# Master_Micro.net
KiCad netlist of a schematic drawn in Altium Designer
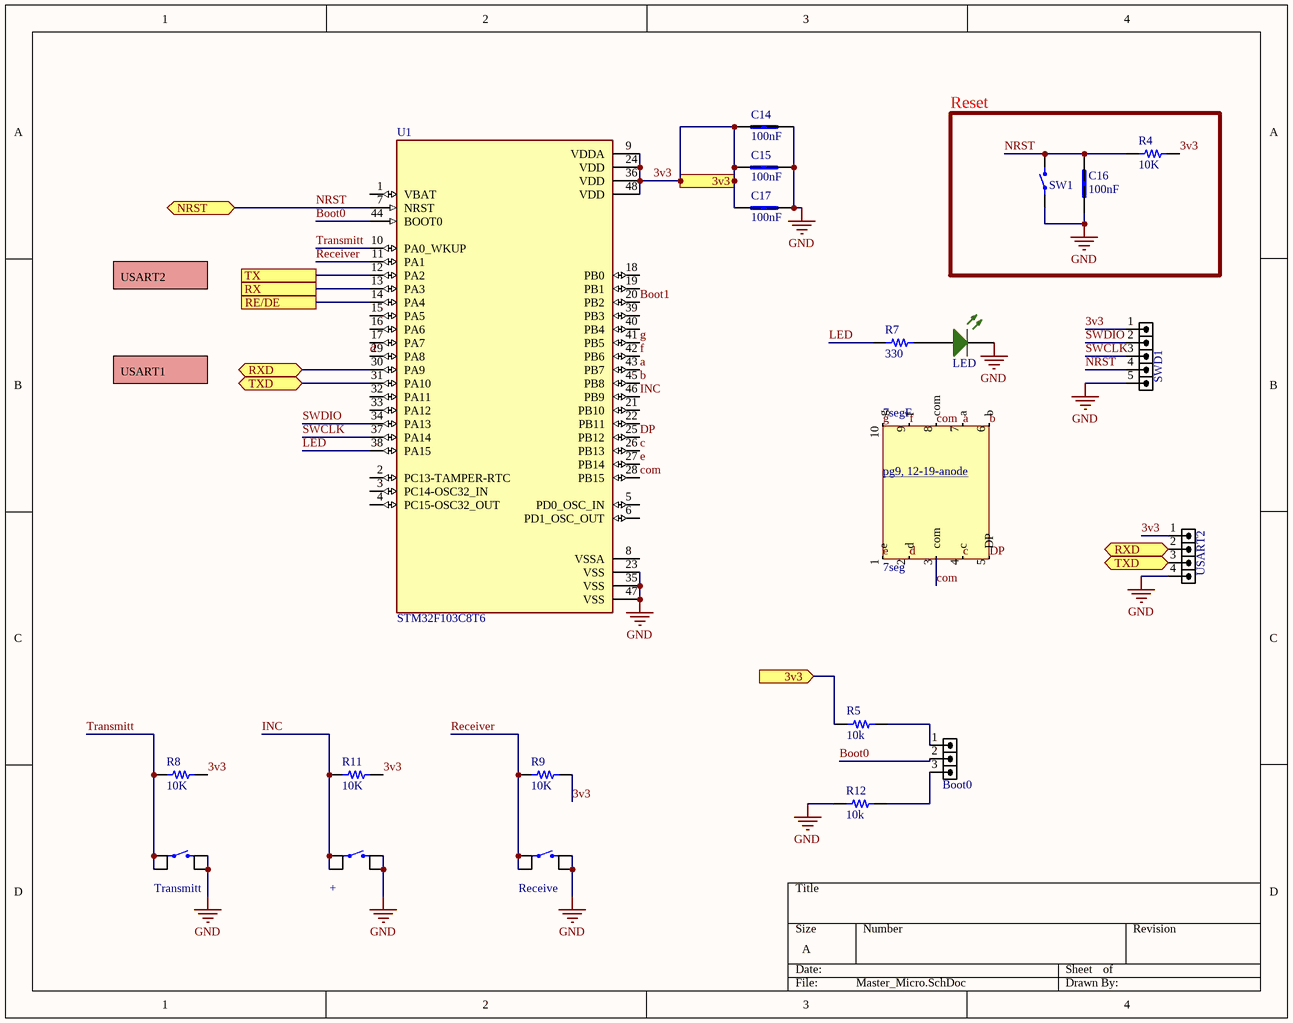
[diagram p0: Master_Micro.SchDoc]

(export (version "E")
  (design (tool "Eeschema 10.0.6"))
  (components
    (comp (ref "+")
      (value "Tactile 4PIN 6X6mm H5mm (THD)")
      (footprint "SWPBT_SPDT_6X6X5SKHH")
      (description "Tactile Switch SPST-NO Top Actuated Surface Mount")
      (fields (field (name "PARTNUMBER") "PTS645SH50SMTR92 LFS"))
      (libsource (lib "Switch") (part "Tactile 4PIN 6X6mm H5mm (THD)"))
    )
    (comp (ref "7seg")
      (value "7seg")
      (footprint "PCBComponent_1 - duplicate")
      (description "file:///C:/Users/Tamana/Downloads/7SEG-12-19mm-GREEN-ANOD.pdf")
      (libsource (lib "7seg") (part "7seg"))
    )
    (comp (ref "Boot0")
      (value "HDRM3")
      (footprint "HDR_1X3")
      (description "CONN, HEADER, Male, pitch: 2.54mm, 3POS")
      (libsource (lib "Conn Header") (part "HDR_1X3"))
    )
    (comp (ref "C14")
      (value "100nF")
      (footprint "CAP 0805_2012")
      (description "COMMERCIAL CHIP STD JAPAN BULK - FN TAPE/REEL, 7 INCH PAPER TAPE-0805")
      (fields (field (name "MP") "LD051C182KAB2A"))
      (libsource (lib "cap 0805") (part "LD051C182KAB2A"))
    )
    (comp (ref "C15")
      (value "100nF")
      (footprint "CAP 0805_2012")
      (description "COMMERCIAL CHIP STD JAPAN BULK - FN TAPE/REEL, 7 INCH PAPER TAPE-0805")
      (fields (field (name "MP") "LD051C182KAB2A"))
      (libsource (lib "cap 0805") (part "LD051C182KAB2A"))
    )
    (comp (ref "C16")
      (value "100nF")
      (footprint "CAP 0805_2012")
      (description "COMMERCIAL CHIP STD JAPAN BULK - FN TAPE/REEL, 7 INCH PAPER TAPE-0805")
      (fields (field (name "MP") "LD051C182KAB2A"))
      (libsource (lib "") (part "LD051C182KAB2A_1"))
    )
    (comp (ref "C17")
      (value "100nF")
      (footprint "CAP 0805_2012")
      (description "COMMERCIAL CHIP STD JAPAN BULK - FN TAPE/REEL, 7 INCH PAPER TAPE-0805")
      (fields (field (name "MP") "LD051C182KAB2A"))
      (libsource (lib "cap 0805") (part "LD051C182KAB2A"))
    )
    (comp (ref "LED")
      (value "LED SMD 0805 GREEN")
      (footprint "LED_0805_GREEN")
      (libsource (lib "Led") (part "LED SMD 0805 GREEN"))
    )
    (comp (ref "R4")
      (value "10K")
      (footprint "RES 0805_2012")
      (description "SMT Resistor")
      (libsource (lib "Resistor") (part "Res 0805"))
    )
    (comp (ref "R5")
      (value "10k")
      (footprint "RES 0805_2012")
      (description "SMT Resistor")
      (libsource (lib "Resistor") (part "Res 0805"))
    )
    (comp (ref "R7")
      (value "330")
      (footprint "RES 0805_2012")
      (description "SMT Resistor")
      (libsource (lib "Resistor") (part "Res 0805"))
    )
    (comp (ref "R8")
      (value "10K")
      (footprint "RES 0805_2012")
      (description "SMT Resistor")
      (libsource (lib "Resistor") (part "Res 0805"))
    )
    (comp (ref "R9")
      (value "10K")
      (footprint "RES 0805_2012")
      (description "SMT Resistor")
      (libsource (lib "Resistor") (part "Res 0805"))
    )
    (comp (ref "R11")
      (value "10K")
      (footprint "RES 0805_2012")
      (description "SMT Resistor")
      (libsource (lib "Resistor") (part "Res 0805"))
    )
    (comp (ref "R12")
      (value "10k")
      (footprint "RES 0805_2012")
      (description "SMT Resistor")
      (libsource (lib "Resistor") (part "Res 0805"))
    )
    (comp (ref "Receive")
      (value "Tactile 4PIN 6X6mm H5mm (THD)")
      (footprint "SWPBT_SPDT_6X6X5SKHH")
      (description "Tactile Switch SPST-NO Top Actuated Surface Mount")
      (fields (field (name "PARTNUMBER") "PTS645SH50SMTR92 LFS"))
      (libsource (lib "Switch") (part "Tactile 4PIN 6X6mm H5mm (THD)"))
    )
    (comp (ref "SW1")
      (value "Tactile 2PIN 6X3.5mm H4.57mm (SMD)")
      (footprint "SWPBS_SPST_6X3X5")
      (description "Tactile Switch SPST-NO Top Actuated Surface Mount")
      (fields (field (name "PARTNUMBER") "FSMSMTR-ND"))
      (libsource (lib "Switch") (part "Tactile 2PIN 6X3.5mm H4.57mm (SMD)"))
    )
    (comp (ref "SWD1")
      (value "HDR1X5")
      (footprint "HDR_1X5")
      (description "CONN, HEADER, Male, pitch: 2.54mm, 5POS")
      (libsource (lib "Conn Header") (part "HDR_1X5"))
    )
    (comp (ref "Transmitt")
      (value "Tactile 4PIN 6X6mm H5mm (THD)")
      (footprint "SWPBT_SPDT_6X6X5SKHH")
      (description "Tactile Switch SPST-NO Top Actuated Surface Mount")
      (fields (field (name "PARTNUMBER") "PTS645SH50SMTR92 LFS"))
      (libsource (lib "Switch") (part "Tactile 4PIN 6X6mm H5mm (THD)"))
    )
    (comp (ref "U1")
      (value "STM32F103C8T6")
      (footprint "QFP50P900X900X160-48N")
      (description "ARM® Cortex®-M3 STM32F1 Microcontroller IC 32-Bit 72MHz 64KB (64K x 8) FLASH 48-LQFP (7x7)")
      (fields (field (name "MF") "STMicroelectronics"))
      (libsource (lib "STM32F103C8T6") (part "STM32F103C8T6"))
    )
    (comp (ref "USART2")
      (value "HDR1X4")
      (footprint "HDR_1X4")
      (description "CONN, HEADER, Male, pitch: 2.54mm, 4POS")
      (libsource (lib "Conn Header") (part "HDR_1X4"))
    )
  )
  (nets
    (net (code "1") (name "/3v3") (class "Default")
      (node (ref "C14") (pin "2") (pinfunction "2_2") (pintype "passive"))
      (node (ref "C15") (pin "2") (pinfunction "2_2") (pintype "passive"))
      (node (ref "C17") (pin "2") (pinfunction "2_2") (pintype "passive"))
      (node (ref "R11") (pin "2") (pinfunction "2_2") (pintype "passive"))
      (node (ref "R4") (pin "2") (pinfunction "2_2") (pintype "passive"))
      (node (ref "R5") (pin "1") (pinfunction "1_1") (pintype "passive"))
      (node (ref "R8") (pin "2") (pinfunction "2_2") (pintype "passive"))
      (node (ref "R9") (pin "2") (pinfunction "2_2") (pintype "passive"))
      (node (ref "SWD1") (pin "1") (pinfunction "1_1") (pintype "passive"))
      (node (ref "U1") (pin "24") (pinfunction "VDD_24") (pintype "power_in"))
      (node (ref "U1") (pin "36") (pinfunction "VDD_36") (pintype "power_in"))
      (node (ref "U1") (pin "48") (pinfunction "VDD_48") (pintype "power_in"))
      (node (ref "U1") (pin "9") (pinfunction "VDDA_9") (pintype "power_in"))
      (node (ref "USART2") (pin "1") (pinfunction "1_1") (pintype "passive"))
    )
    (net (code "2") (name "/Boot0") (class "Default")
      (node (ref "Boot0") (pin "2") (pinfunction "2_2") (pintype "passive"))
      (node (ref "U1") (pin "44") (pinfunction "BOOT0_44") (pintype "input"))
    )
    (net (code "3") (name "/Boot1") (class "Default")
      (node (ref "U1") (pin "20") (pinfunction "PB2_20") (pintype "bidirectional"))
    )
    (net (code "4") (name "/DP") (class "Default")
      (node (ref "7seg") (pin "5") (pinfunction "DP_5") (pintype "passive"))
      (node (ref "U1") (pin "25") (pinfunction "PB12_25") (pintype "bidirectional"))
    )
    (net (code "5") (name "/INC") (class "Default")
      (node (ref "+") (pin "1") (pinfunction "1_1") (pintype "passive"))
      (node (ref "+") (pin "4") (pinfunction "4_4") (pintype "passive"))
      (node (ref "R11") (pin "1") (pinfunction "1_1") (pintype "passive"))
      (node (ref "U1") (pin "46") (pinfunction "PB9_46") (pintype "bidirectional"))
    )
    (net (code "6") (name "/LED") (class "Default")
      (node (ref "R7") (pin "1") (pinfunction "1_1") (pintype "passive"))
      (node (ref "U1") (pin "38") (pinfunction "PA15_38") (pintype "bidirectional"))
    )
    (net (code "7") (name "/NRST") (class "Default")
      (node (ref "C16") (pin "1") (pinfunction "1_1") (pintype "passive"))
      (node (ref "R4") (pin "1") (pinfunction "1_1") (pintype "passive"))
      (node (ref "SW1") (pin "2") (pinfunction "2_2") (pintype "passive"))
      (node (ref "SWD1") (pin "4") (pinfunction "4_4") (pintype "passive"))
      (node (ref "U1") (pin "7") (pinfunction "NRST_7") (pintype "input"))
    )
    (net (code "8") (name "/RE{slash}DE") (class "Default")
      (node (ref "U1") (pin "14") (pinfunction "PA4_14") (pintype "bidirectional"))
    )
    (net (code "9") (name "/RX") (class "Default")
      (node (ref "U1") (pin "13") (pinfunction "PA3_13") (pintype "bidirectional"))
    )
    (net (code "10") (name "/RXD") (class "Default")
      (node (ref "U1") (pin "30") (pinfunction "PA9_30") (pintype "bidirectional"))
      (node (ref "USART2") (pin "2") (pinfunction "2_2") (pintype "passive"))
    )
    (net (code "11") (name "/Receiver") (class "Default")
      (node (ref "R9") (pin "1") (pinfunction "1_1") (pintype "passive"))
      (node (ref "Receive") (pin "1") (pinfunction "1_1") (pintype "passive"))
      (node (ref "Receive") (pin "4") (pinfunction "4_4") (pintype "passive"))
      (node (ref "U1") (pin "11") (pinfunction "PA1_11") (pintype "bidirectional"))
    )
    (net (code "12") (name "/SWCLK") (class "Default")
      (node (ref "SWD1") (pin "3") (pinfunction "3_3") (pintype "passive"))
      (node (ref "U1") (pin "37") (pinfunction "PA14_37") (pintype "bidirectional"))
    )
    (net (code "13") (name "/SWDIO") (class "Default")
      (node (ref "SWD1") (pin "2") (pinfunction "2_2") (pintype "passive"))
      (node (ref "U1") (pin "34") (pinfunction "PA13_34") (pintype "bidirectional"))
    )
    (net (code "14") (name "/TX") (class "Default")
      (node (ref "U1") (pin "12") (pinfunction "PA2_12") (pintype "bidirectional"))
    )
    (net (code "15") (name "/TXD") (class "Default")
      (node (ref "U1") (pin "31") (pinfunction "PA10_31") (pintype "bidirectional"))
      (node (ref "USART2") (pin "3") (pinfunction "3_3") (pintype "passive"))
    )
    (net (code "16") (name "/Transmitt") (class "Default")
      (node (ref "R8") (pin "1") (pinfunction "1_1") (pintype "passive"))
      (node (ref "Transmitt") (pin "1") (pinfunction "1_1") (pintype "passive"))
      (node (ref "Transmitt") (pin "4") (pinfunction "4_4") (pintype "passive"))
      (node (ref "U1") (pin "10") (pinfunction "PA0_WKUP_10") (pintype "bidirectional"))
    )
    (net (code "17") (name "/a") (class "Default")
      (node (ref "7seg") (pin "7") (pinfunction "a_7") (pintype "passive"))
      (node (ref "U1") (pin "43") (pinfunction "PB7_43") (pintype "bidirectional"))
    )
    (net (code "18") (name "/b") (class "Default")
      (node (ref "7seg") (pin "6") (pinfunction "b_6") (pintype "passive"))
      (node (ref "U1") (pin "45") (pinfunction "PB8_45") (pintype "bidirectional"))
    )
    (net (code "19") (name "/c") (class "Default")
      (node (ref "7seg") (pin "4") (pinfunction "c_4") (pintype "passive"))
      (node (ref "U1") (pin "26") (pinfunction "PB13_26") (pintype "bidirectional"))
    )
    (net (code "20") (name "/com") (class "Default")
      (node (ref "7seg") (pin "3") (pinfunction "com_3") (pintype "passive"))
      (node (ref "7seg") (pin "8") (pinfunction "com_8") (pintype "passive"))
      (node (ref "U1") (pin "28") (pinfunction "PB15_28") (pintype "bidirectional"))
    )
    (net (code "21") (name "/d") (class "Default")
      (node (ref "7seg") (pin "2") (pinfunction "d_2") (pintype "passive"))
      (node (ref "U1") (pin "29") (pinfunction "PA8_29") (pintype "bidirectional"))
    )
    (net (code "22") (name "/e") (class "Default")
      (node (ref "7seg") (pin "1") (pinfunction "e_1") (pintype "passive"))
      (node (ref "U1") (pin "27") (pinfunction "PB14_27") (pintype "bidirectional"))
    )
    (net (code "23") (name "/f") (class "Default")
      (node (ref "7seg") (pin "9") (pinfunction "f_9") (pintype "passive"))
      (node (ref "U1") (pin "42") (pinfunction "PB6_42") (pintype "bidirectional"))
    )
    (net (code "24") (name "/g") (class "Default")
      (node (ref "7seg") (pin "10") (pinfunction "g_10") (pintype "passive"))
      (node (ref "U1") (pin "41") (pinfunction "PB5_41") (pintype "bidirectional"))
    )
    (net (code "25") (name "GND") (class "Default")
      (node (ref "+") (pin "2") (pinfunction "2_2") (pintype "passive"))
      (node (ref "+") (pin "3") (pinfunction "3_3") (pintype "passive"))
      (node (ref "C14") (pin "1") (pinfunction "1_1") (pintype "passive"))
      (node (ref "C15") (pin "1") (pinfunction "1_1") (pintype "passive"))
      (node (ref "C16") (pin "2") (pinfunction "2_2") (pintype "passive"))
      (node (ref "C17") (pin "1") (pinfunction "1_1") (pintype "passive"))
      (node (ref "LED") (pin "2") (pinfunction "K_2") (pintype "passive"))
      (node (ref "R12") (pin "1") (pinfunction "1_1") (pintype "passive"))
      (node (ref "Receive") (pin "2") (pinfunction "2_2") (pintype "passive"))
      (node (ref "Receive") (pin "3") (pinfunction "3_3") (pintype "passive"))
      (node (ref "SW1") (pin "1") (pinfunction "1_1") (pintype "passive"))
      (node (ref "SWD1") (pin "5") (pinfunction "5_5") (pintype "passive"))
      (node (ref "Transmitt") (pin "2") (pinfunction "2_2") (pintype "passive"))
      (node (ref "Transmitt") (pin "3") (pinfunction "3_3") (pintype "passive"))
      (node (ref "U1") (pin "23") (pinfunction "VSS_23") (pintype "power_in"))
      (node (ref "U1") (pin "35") (pinfunction "VSS_35") (pintype "power_in"))
      (node (ref "U1") (pin "47") (pinfunction "VSS_47") (pintype "power_in"))
      (node (ref "USART2") (pin "4") (pinfunction "4_4") (pintype "passive"))
    )
    (net (code "26") (name "Net-(Boot0-Pad1)") (class "Default")
      (node (ref "Boot0") (pin "1") (pinfunction "1_1") (pintype "passive"))
      (node (ref "R5") (pin "2") (pinfunction "2_2") (pintype "passive"))
    )
    (net (code "27") (name "Net-(Boot0-Pad3)") (class "Default")
      (node (ref "Boot0") (pin "3") (pinfunction "3_3") (pintype "passive"))
      (node (ref "R12") (pin "2") (pinfunction "2_2") (pintype "passive"))
    )
    (net (code "28") (name "Net-(LED-A)") (class "Default")
      (node (ref "LED") (pin "1") (pinfunction "A_1") (pintype "passive"))
      (node (ref "R7") (pin "2") (pinfunction "2_2") (pintype "passive"))
    )
    (net (code "29") (name "unconnected-(U1-PA5-Pad15)") (class "Default")
      (node (ref "U1") (pin "15") (pinfunction "PA5_15") (pintype "bidirectional"))
    )
    (net (code "30") (name "unconnected-(U1-PA6-Pad16)") (class "Default")
      (node (ref "U1") (pin "16") (pinfunction "PA6_16") (pintype "bidirectional"))
    )
    (net (code "31") (name "unconnected-(U1-PA7-Pad17)") (class "Default")
      (node (ref "U1") (pin "17") (pinfunction "PA7_17") (pintype "bidirectional"))
    )
    (net (code "32") (name "unconnected-(U1-PA11-Pad32)") (class "Default")
      (node (ref "U1") (pin "32") (pinfunction "PA11_32") (pintype "bidirectional"))
    )
    (net (code "33") (name "unconnected-(U1-PA12-Pad33)") (class "Default")
      (node (ref "U1") (pin "33") (pinfunction "PA12_33") (pintype "bidirectional"))
    )
    (net (code "34") (name "unconnected-(U1-PB0-Pad18)") (class "Default")
      (node (ref "U1") (pin "18") (pinfunction "PB0_18") (pintype "bidirectional"))
    )
    (net (code "35") (name "unconnected-(U1-PB1-Pad19)") (class "Default")
      (node (ref "U1") (pin "19") (pinfunction "PB1_19") (pintype "bidirectional"))
    )
    (net (code "36") (name "unconnected-(U1-PB3-Pad39)") (class "Default")
      (node (ref "U1") (pin "39") (pinfunction "PB3_39") (pintype "bidirectional"))
    )
    (net (code "37") (name "unconnected-(U1-PB4-Pad40)") (class "Default")
      (node (ref "U1") (pin "40") (pinfunction "PB4_40") (pintype "bidirectional"))
    )
    (net (code "38") (name "unconnected-(U1-PB10-Pad21)") (class "Default")
      (node (ref "U1") (pin "21") (pinfunction "PB10_21") (pintype "bidirectional"))
    )
    (net (code "39") (name "unconnected-(U1-PB11-Pad22)") (class "Default")
      (node (ref "U1") (pin "22") (pinfunction "PB11_22") (pintype "bidirectional"))
    )
    (net (code "40") (name "unconnected-(U1-PC13-TAMPER-RTC-Pad2)") (class "Default")
      (node (ref "U1") (pin "2") (pinfunction "PC13-TAMPER-RTC_2") (pintype "bidirectional"))
    )
    (net (code "41") (name "unconnected-(U1-PC14-OSC32_IN-Pad3)") (class "Default")
      (node (ref "U1") (pin "3") (pinfunction "PC14-OSC32_IN_3") (pintype "bidirectional"))
    )
    (net (code "42") (name "unconnected-(U1-PC15-OSC32_OUT-Pad4)") (class "Default")
      (node (ref "U1") (pin "4") (pinfunction "PC15-OSC32_OUT_4") (pintype "bidirectional"))
    )
    (net (code "43") (name "unconnected-(U1-PD0_OSC_IN-Pad5)") (class "Default")
      (node (ref "U1") (pin "5") (pinfunction "PD0_OSC_IN_5") (pintype "bidirectional"))
    )
    (net (code "44") (name "unconnected-(U1-PD1_OSC_OUT-Pad6)") (class "Default")
      (node (ref "U1") (pin "6") (pinfunction "PD1_OSC_OUT_6") (pintype "bidirectional"))
    )
    (net (code "45") (name "unconnected-(U1-VBAT-Pad1)") (class "Default")
      (node (ref "U1") (pin "1") (pinfunction "VBAT_1") (pintype "bidirectional"))
    )
    (net (code "46") (name "unconnected-(U1-VSSA-Pad8)") (class "Default")
      (node (ref "U1") (pin "8") (pinfunction "VSSA_8") (pintype "power_in"))
    )
  )
)
